# v1_0.net
KiCad netlist of a schematic drawn in Altium Designer
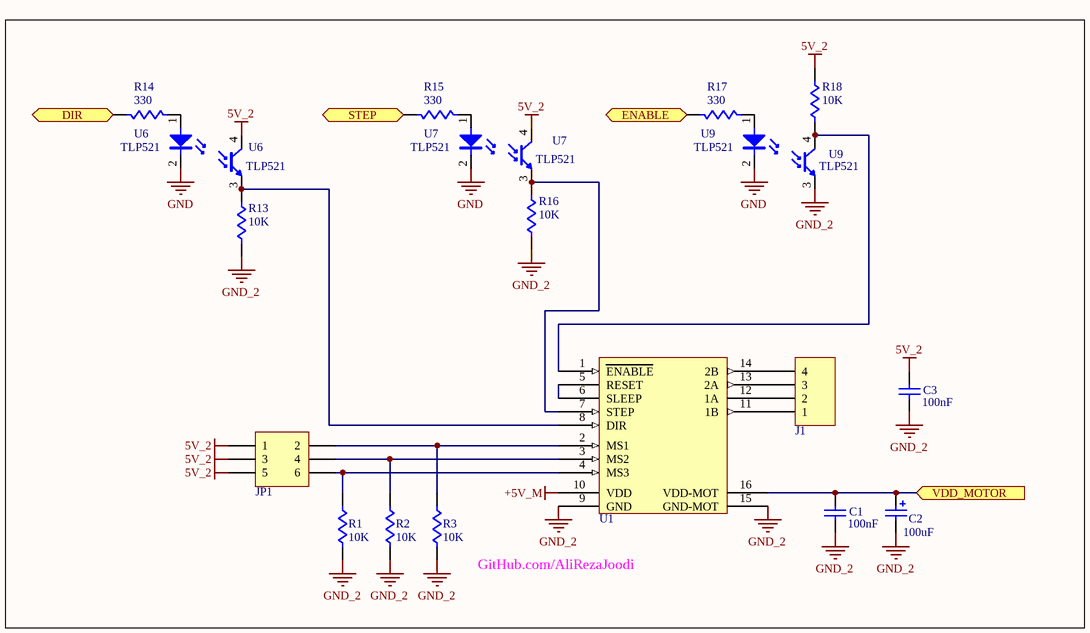
[diagram p0: v1.0.SchDoc]

(export (version "E")
  (design (tool "Eeschema 10.0.6"))
  (components
    (comp (ref "C1")
      (value "C1")
      (footprint "CAPNTO2.54-3.05x1.78A")
      (description "Capacitor")
      (fields
        (field (name "MANUFACTURER") "Generic Components")
        (field (name "ALTIUM_VALUE") "100nF")
        (field (name "PUBLISHER") "Altium Limited")
      )
      (libsource (lib "Miscellaneous Devices") (part "Cap"))
    )
    (comp (ref "C2")
      (value "C2")
      (footprint "CAPPR3.05-3.81x6.35")
      (description "Polarized Capacitor (Radial)")
      (fields
        (field (name "MANUFACTURER") "Generic Components")
        (field (name "ALTIUM_VALUE") "100uF")
        (field (name "PUBLISHER") "Altium Limited")
      )
      (libsource (lib "Miscellaneous Devices") (part "Cap Pol1"))
    )
    (comp (ref "C3")
      (value "C3")
      (footprint "CAPNTO2.54-3.05x1.78A")
      (description "Capacitor")
      (fields
        (field (name "MANUFACTURER") "Generic Components")
        (field (name "ALTIUM_VALUE") "100nF")
        (field (name "PUBLISHER") "Altium Limited")
      )
      (libsource (lib "Miscellaneous Devices") (part "Cap"))
    )
    (comp (ref "J1")
      (value "J1")
      (footprint "Fonics_4PIN_1")
      (description "Header, 4-Pin")
      (fields (field (name "MANUFACTURER") "Generic Components") (field (name "PUBLISHER") "Altium Limited"))
      (libsource (lib "Miscellaneous Connectors") (part "Header 4"))
    )
    (comp (ref "JP1")
      (value "JP1")
      (footprint "HDR2X3")
      (description "Header, 3-Pin, Dual row")
      (fields (field (name "MANUFACTURER") "Generic Components") (field (name "PUBLISHER") "Altium Limited"))
      (libsource (lib "Miscellaneous Connectors") (part "Header 3X2"))
    )
    (comp (ref "R1")
      (value "R1")
      (footprint "AXIAL-0.4")
      (description "Resistor")
      (fields
        (field (name "MANUFACTURER") "Generic Components")
        (field (name "ALTIUM_VALUE") "10K")
        (field (name "PUBLISHER") "Altium Limited")
      )
      (libsource (lib "Miscellaneous Devices") (part "Res1"))
    )
    (comp (ref "R2")
      (value "R2")
      (footprint "AXIAL-0.4")
      (description "Resistor")
      (fields
        (field (name "MANUFACTURER") "Generic Components")
        (field (name "ALTIUM_VALUE") "10K")
        (field (name "PUBLISHER") "Altium Limited")
      )
      (libsource (lib "Miscellaneous Devices") (part "Res1"))
    )
    (comp (ref "R3")
      (value "R3")
      (footprint "AXIAL-0.4")
      (description "Resistor")
      (fields
        (field (name "MANUFACTURER") "Generic Components")
        (field (name "ALTIUM_VALUE") "10K")
        (field (name "PUBLISHER") "Altium Limited")
      )
      (libsource (lib "Miscellaneous Devices") (part "Res1"))
    )
    (comp (ref "R13")
      (value "R13")
      (footprint "AXIAL-0.4")
      (description "Resistor")
      (fields
        (field (name "MANUFACTURER") "Generic Components")
        (field (name "ALTIUM_VALUE") "10K")
        (field (name "PUBLISHER") "Altium Limited")
      )
      (libsource (lib "Miscellaneous Devices") (part "Res1"))
    )
    (comp (ref "R14")
      (value "R14")
      (footprint "AXIAL-0.4")
      (description "Resistor")
      (fields
        (field (name "MANUFACTURER") "Generic Components")
        (field (name "ALTIUM_VALUE") "330")
        (field (name "PUBLISHER") "Altium Limited")
      )
      (libsource (lib "Miscellaneous Devices") (part "Res1"))
    )
    (comp (ref "R15")
      (value "R15")
      (footprint "AXIAL-0.4")
      (description "Resistor")
      (fields
        (field (name "MANUFACTURER") "Generic Components")
        (field (name "ALTIUM_VALUE") "330")
        (field (name "PUBLISHER") "Altium Limited")
      )
      (libsource (lib "Miscellaneous Devices") (part "Res1"))
    )
    (comp (ref "R16")
      (value "R16")
      (footprint "AXIAL-0.4")
      (description "Resistor")
      (fields
        (field (name "MANUFACTURER") "Generic Components")
        (field (name "ALTIUM_VALUE") "10K")
        (field (name "PUBLISHER") "Altium Limited")
      )
      (libsource (lib "Miscellaneous Devices") (part "Res1"))
    )
    (comp (ref "R17")
      (value "R17")
      (footprint "AXIAL-0.4")
      (description "Resistor")
      (fields
        (field (name "MANUFACTURER") "Generic Components")
        (field (name "ALTIUM_VALUE") "330")
        (field (name "PUBLISHER") "Altium Limited")
      )
      (libsource (lib "Miscellaneous Devices") (part "Res1"))
    )
    (comp (ref "R18")
      (value "R18")
      (footprint "AXIAL-0.4")
      (description "Resistor")
      (fields
        (field (name "MANUFACTURER") "Generic Components")
        (field (name "ALTIUM_VALUE") "10K")
        (field (name "PUBLISHER") "Altium Limited")
      )
      (libsource (lib "Miscellaneous Devices") (part "Res1"))
    )
    (comp (ref "U1")
      (value "U1")
      (footprint "Reprap-A4988")
      (description "Reprap-A4988")
      (libsource (lib "my Libraries") (part "Reprap-A4988"))
    )
    (comp (ref "U6")
      (value "U6")
      (footprint "DIP4e")
      (description "Optoisolator")
      (fields (field (name "ALTIUM_VALUE") "TLP521") (field (name "PUBLISHER") "Altium Limited"))
      (libsource (lib "my Libraries") (part "Optoisolator"))
    )
    (comp (ref "U7")
      (value "U7")
      (footprint "DIP4e")
      (description "Optoisolator")
      (fields (field (name "ALTIUM_VALUE") "TLP521") (field (name "PUBLISHER") "Altium Limited"))
      (libsource (lib "my Libraries") (part "Optoisolator"))
    )
    (comp (ref "U9")
      (value "U9")
      (footprint "DIP4e")
      (description "Optoisolator")
      (fields (field (name "ALTIUM_VALUE") "TLP521") (field (name "PUBLISHER") "Altium Limited"))
      (libsource (lib "my Libraries") (part "Optoisolator"))
    )
  )
  (nets
    (net (code "1") (name "+5V_M") (class "Default")
      (node (ref "U1") (pin "10") (pinfunction "VDD_10") (pintype "power_in"))
    )
    (net (code "2") (name "/DIR") (class "Default")
      (node (ref "R14") (pin "2") (pinfunction "2_2") (pintype "passive"))
    )
    (net (code "3") (name "/ENABLE") (class "Default")
      (node (ref "R17") (pin "2") (pinfunction "2_2") (pintype "passive"))
    )
    (net (code "4") (name "/STEP") (class "Default")
      (node (ref "R15") (pin "2") (pinfunction "2_2") (pintype "passive"))
    )
    (net (code "5") (name "/VDD_MOTOR") (class "Default")
      (node (ref "C1") (pin "1") (pinfunction "1_1") (pintype "passive"))
      (node (ref "C2") (pin "1") (pinfunction "1_1") (pintype "passive"))
      (node (ref "U1") (pin "16") (pinfunction "VDD-MOT_16") (pintype "power_in"))
    )
    (net (code "6") (name "5V_2") (class "Default")
      (node (ref "C3") (pin "1") (pinfunction "1_1") (pintype "passive"))
      (node (ref "JP1") (pin "1") (pinfunction "1_1") (pintype "passive"))
      (node (ref "JP1") (pin "3") (pinfunction "3_3") (pintype "passive"))
      (node (ref "JP1") (pin "5") (pinfunction "5_5") (pintype "passive"))
      (node (ref "R18") (pin "1") (pinfunction "1_1") (pintype "passive"))
      (node (ref "U6") (pin "4") (pinfunction "C_4") (pintype "passive"))
      (node (ref "U7") (pin "4") (pinfunction "C_4") (pintype "passive"))
    )
    (net (code "7") (name "GND") (class "Default")
      (node (ref "U6") (pin "2") (pinfunction "K_2") (pintype "power_in"))
      (node (ref "U7") (pin "2") (pinfunction "K_2") (pintype "power_in"))
      (node (ref "U9") (pin "2") (pinfunction "K_2") (pintype "power_in"))
    )
    (net (code "8") (name "GND_2") (class "Default")
      (node (ref "C1") (pin "2") (pinfunction "2_2") (pintype "passive"))
      (node (ref "C2") (pin "2") (pinfunction "2_2") (pintype "passive"))
      (node (ref "C3") (pin "2") (pinfunction "2_2") (pintype "passive"))
      (node (ref "R1") (pin "2") (pinfunction "2_2") (pintype "passive"))
      (node (ref "R13") (pin "2") (pinfunction "2_2") (pintype "passive"))
      (node (ref "R16") (pin "2") (pinfunction "2_2") (pintype "passive"))
      (node (ref "R2") (pin "2") (pinfunction "2_2") (pintype "passive"))
      (node (ref "R3") (pin "2") (pinfunction "2_2") (pintype "passive"))
      (node (ref "U1") (pin "15") (pinfunction "GND-MOT_15") (pintype "power_in"))
      (node (ref "U1") (pin "9") (pinfunction "GND_9") (pintype "power_in"))
      (node (ref "U9") (pin "3") (pinfunction "E_3") (pintype "passive"))
    )
    (net (code "9") (name "Net-(U1-1A)") (class "Default")
      (node (ref "J1") (pin "2") (pinfunction "2_2") (pintype "passive"))
      (node (ref "U1") (pin "12") (pinfunction "1A_12") (pintype "passive"))
    )
    (net (code "10") (name "Net-(U1-1B)") (class "Default")
      (node (ref "J1") (pin "1") (pinfunction "1_1") (pintype "passive"))
      (node (ref "U1") (pin "11") (pinfunction "1B_11") (pintype "output"))
    )
    (net (code "11") (name "Net-(U1-2A)") (class "Default")
      (node (ref "J1") (pin "3") (pinfunction "3_3") (pintype "passive"))
      (node (ref "U1") (pin "13") (pinfunction "2A_13") (pintype "output"))
    )
    (net (code "12") (name "Net-(U1-2B)") (class "Default")
      (node (ref "J1") (pin "4") (pinfunction "4_4") (pintype "passive"))
      (node (ref "U1") (pin "14") (pinfunction "2B_14") (pintype "output"))
    )
    (net (code "13") (name "Net-(U1-DIR)") (class "Default")
      (node (ref "R13") (pin "1") (pinfunction "1_1") (pintype "passive"))
      (node (ref "U1") (pin "8") (pinfunction "DIR_8") (pintype "input"))
      (node (ref "U6") (pin "3") (pinfunction "E_3") (pintype "passive"))
    )
    (net (code "14") (name "Net-(U1-ENABLE)") (class "Default")
      (node (ref "R18") (pin "2") (pinfunction "2_2") (pintype "passive"))
      (node (ref "U1") (pin "1") (pinfunction "ENABLE_1") (pintype "input"))
      (node (ref "U9") (pin "4") (pinfunction "C_4") (pintype "passive"))
    )
    (net (code "15") (name "Net-(U1-MS1)") (class "Default")
      (node (ref "JP1") (pin "2") (pinfunction "2_2") (pintype "passive"))
      (node (ref "R3") (pin "1") (pinfunction "1_1") (pintype "passive"))
      (node (ref "U1") (pin "2") (pinfunction "MS1_2") (pintype "input"))
    )
    (net (code "16") (name "Net-(U1-MS2)") (class "Default")
      (node (ref "JP1") (pin "4") (pinfunction "4_4") (pintype "passive"))
      (node (ref "R2") (pin "1") (pinfunction "1_1") (pintype "passive"))
      (node (ref "U1") (pin "3") (pinfunction "MS2_3") (pintype "input"))
    )
    (net (code "17") (name "Net-(U1-MS3)") (class "Default")
      (node (ref "JP1") (pin "6") (pinfunction "6_6") (pintype "passive"))
      (node (ref "R1") (pin "1") (pinfunction "1_1") (pintype "passive"))
      (node (ref "U1") (pin "4") (pinfunction "MS3_4") (pintype "input"))
    )
    (net (code "18") (name "Net-(U1-RESET)") (class "Default")
      (node (ref "U1") (pin "5") (pinfunction "RESET_5") (pintype "passive"))
      (node (ref "U1") (pin "6") (pinfunction "SLEEP_6") (pintype "passive"))
    )
    (net (code "19") (name "Net-(U1-STEP)") (class "Default")
      (node (ref "R16") (pin "1") (pinfunction "1_1") (pintype "passive"))
      (node (ref "U1") (pin "7") (pinfunction "STEP_7") (pintype "input"))
      (node (ref "U7") (pin "3") (pinfunction "E_3") (pintype "passive"))
    )
    (net (code "20") (name "Net-(U6A-A)") (class "Default")
      (node (ref "R14") (pin "1") (pinfunction "1_1") (pintype "passive"))
      (node (ref "U6") (pin "1") (pinfunction "A_1") (pintype "power_in"))
    )
    (net (code "21") (name "Net-(U7A-A)") (class "Default")
      (node (ref "R15") (pin "1") (pinfunction "1_1") (pintype "passive"))
      (node (ref "U7") (pin "1") (pinfunction "A_1") (pintype "power_in"))
    )
    (net (code "22") (name "Net-(U9A-A)") (class "Default")
      (node (ref "R17") (pin "1") (pinfunction "1_1") (pintype "passive"))
      (node (ref "U9") (pin "1") (pinfunction "A_1") (pintype "power_in"))
    )
  )
)
